# power.net
KiCad netlist of a schematic drawn in Altium Designer
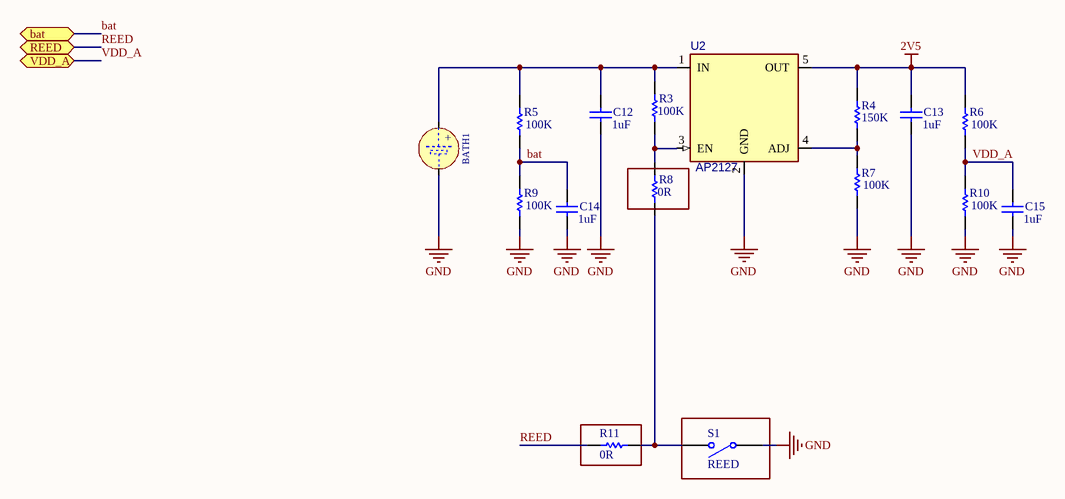
[diagram p0: power.SchDoc]

(export (version "E")
  (design (tool "Eeschema 10.0.6"))
  (components
    (comp (ref "BATH1")
      (value "~")
      (footprint "BATH_KEYSTONE_3000")
      (description "Battery Holder whit 2 Pin")
      (fields
        (field (name "PART NUMBER") "BATH_KEYSTONE_3000")
        (field (name "MANUFACTURER") "KEYSTONE")
        (field (name "AUTHOR") "CERN DEM JLC")
      )
      (libsource (lib "Eletro-mechanical") (part "Battery Holder 2 Pin"))
    )
    (comp (ref "C12")
      (value "1uF")
      (footprint "0805")
      (description "Ceramic Chip Capacitor - Standard")
      (fields (field (name "Comment") "C0805") (field (name "PUBLISHER") "Altium Limited"))
      (libsource (lib "KEMET Chip Capacitor") (part "C0805"))
    )
    (comp (ref "C13")
      (value "1uF")
      (footprint "0805")
      (description "Ceramic Chip Capacitor - Standard")
      (fields (field (name "Comment") "C0805") (field (name "PUBLISHER") "Altium Limited"))
      (libsource (lib "KEMET Chip Capacitor") (part "C0805"))
    )
    (comp (ref "C14")
      (value "1uF")
      (footprint "0805")
      (description "Ceramic Chip Capacitor - Standard")
      (fields (field (name "Comment") "C0805") (field (name "PUBLISHER") "Altium Limited"))
      (libsource (lib "KEMET Chip Capacitor") (part "C0805"))
    )
    (comp (ref "C15")
      (value "1uF")
      (footprint "0805")
      (description "Ceramic Chip Capacitor - Standard")
      (fields (field (name "Comment") "C0805") (field (name "PUBLISHER") "Altium Limited"))
      (libsource (lib "KEMET Chip Capacitor") (part "C0805"))
    )
    (comp (ref "R3")
      (value "100K")
      (footprint "ERA-0805")
      (fields (field (name "Comment") "ERA6Y") (field (name "PUBLISHER") "Altium Limited"))
      (libsource (lib "Panasonic Resistor_yeni") (part "ERA6Y"))
    )
    (comp (ref "R4")
      (value "150K")
      (footprint "ERA-0805")
      (fields (field (name "Comment") "ERA6Y") (field (name "PUBLISHER") "Altium Limited"))
      (libsource (lib "Panasonic Resistor_yeni") (part "ERA6Y"))
    )
    (comp (ref "R5")
      (value "100K")
      (footprint "ERA-0805")
      (fields (field (name "Comment") "ERA6Y") (field (name "PUBLISHER") "Altium Limited"))
      (libsource (lib "Panasonic Resistor_yeni") (part "ERA6Y"))
    )
    (comp (ref "R6")
      (value "100K")
      (footprint "ERA-0805")
      (fields (field (name "Comment") "ERA6Y") (field (name "PUBLISHER") "Altium Limited"))
      (libsource (lib "Panasonic Resistor_yeni") (part "ERA6Y"))
    )
    (comp (ref "R7")
      (value "100K")
      (footprint "ERA-0805")
      (fields (field (name "Comment") "ERA6Y") (field (name "PUBLISHER") "Altium Limited"))
      (libsource (lib "Panasonic Resistor_yeni") (part "ERA6Y"))
    )
    (comp (ref "R8")
      (value "0R")
      (footprint "ERA-0805")
      (fields (field (name "Comment") "ERA6Y") (field (name "PUBLISHER") "Altium Limited"))
      (libsource (lib "Panasonic Resistor_yeni") (part "ERA6Y"))
    )
    (comp (ref "R9")
      (value "100K")
      (footprint "ERA-0805")
      (fields (field (name "Comment") "ERA6Y") (field (name "PUBLISHER") "Altium Limited"))
      (libsource (lib "Panasonic Resistor_yeni") (part "ERA6Y"))
    )
    (comp (ref "R10")
      (value "100K")
      (footprint "ERA-0805")
      (fields (field (name "Comment") "ERA6Y") (field (name "PUBLISHER") "Altium Limited"))
      (libsource (lib "Panasonic Resistor_yeni") (part "ERA6Y"))
    )
    (comp (ref "R11")
      (value "0R")
      (footprint "ERA-0805")
      (fields (field (name "Comment") "ERA6Y") (field (name "PUBLISHER") "Altium Limited"))
      (libsource (lib "Panasonic Resistor_yeni") (part "ERA6Y"))
    )
    (comp (ref "S1")
      (value "REED")
      (footprint "SPST-2")
      (description "Single-Pole, Single-Throw Switch")
      (fields (field (name "PUBLISHER") "Altium Limited"))
      (libsource (lib "Miscellaneous Devices") (part "SW-SPST"))
    )
    (comp (ref "U2")
      (value "AP2127")
      (footprint "SOT-25")
      (description "LDO 300mA,  Low Quiescent Current, Fast Transient")
      (fields (field (name "Comment") "000000"))
      (libsource (lib "diodes-inc") (part "AP7331-WG"))
    )
  )
  (nets
    (net (code "1") (name "/REED") (class "Default")
      (node (ref "R11") (pin "2") (pinfunction "2_2") (pintype "passive"))
    )
    (net (code "2") (name "/VDD_A") (class "Default")
      (node (ref "C15") (pin "2") (pinfunction "2_2") (pintype "passive"))
      (node (ref "R10") (pin "2") (pinfunction "2_2") (pintype "passive"))
      (node (ref "R6") (pin "1") (pinfunction "1_1") (pintype "passive"))
    )
    (net (code "3") (name "/bat") (class "Default")
      (node (ref "C14") (pin "2") (pinfunction "2_2") (pintype "passive"))
      (node (ref "R5") (pin "1") (pinfunction "1_1") (pintype "passive"))
      (node (ref "R9") (pin "2") (pinfunction "2_2") (pintype "passive"))
    )
    (net (code "4") (name "2V5") (class "Default")
      (node (ref "C13") (pin "2") (pinfunction "2_2") (pintype "passive"))
      (node (ref "R4") (pin "2") (pinfunction "2_2") (pintype "passive"))
      (node (ref "R6") (pin "2") (pinfunction "2_2") (pintype "passive"))
      (node (ref "U2") (pin "5") (pinfunction "OUT_5") (pintype "power_in"))
    )
    (net (code "5") (name "GND") (class "Default")
      (node (ref "BATH1") (pin "2") (pinfunction "MINUS_2") (pintype "power_in"))
      (node (ref "C12") (pin "1") (pinfunction "1_1") (pintype "passive"))
      (node (ref "C13") (pin "1") (pinfunction "1_1") (pintype "passive"))
      (node (ref "C14") (pin "1") (pinfunction "1_1") (pintype "passive"))
      (node (ref "C15") (pin "1") (pinfunction "1_1") (pintype "passive"))
      (node (ref "R10") (pin "1") (pinfunction "1_1") (pintype "passive"))
      (node (ref "R7") (pin "1") (pinfunction "1_1") (pintype "passive"))
      (node (ref "R9") (pin "1") (pinfunction "1_1") (pintype "passive"))
      (node (ref "S1") (pin "1") (pinfunction "COMMON_1") (pintype "passive"))
      (node (ref "U2") (pin "2") (pinfunction "GND_2") (pintype "power_in"))
    )
    (net (code "6") (name "Net-(BATH1-PLUS)") (class "Default")
      (node (ref "BATH1") (pin "1") (pinfunction "PLUS_1") (pintype "power_in"))
      (node (ref "C12") (pin "2") (pinfunction "2_2") (pintype "passive"))
      (node (ref "R3") (pin "2") (pinfunction "2_2") (pintype "passive"))
      (node (ref "R5") (pin "2") (pinfunction "2_2") (pintype "passive"))
      (node (ref "U2") (pin "1") (pinfunction "IN_1") (pintype "power_in"))
    )
    (net (code "7") (name "Net-(S1-NO)") (class "Default")
      (node (ref "R11") (pin "1") (pinfunction "1_1") (pintype "passive"))
      (node (ref "R8") (pin "1") (pinfunction "1_1") (pintype "passive"))
      (node (ref "S1") (pin "2") (pinfunction "NO_2") (pintype "passive"))
    )
    (net (code "8") (name "Net-(U2-ADJ)") (class "Default")
      (node (ref "R4") (pin "1") (pinfunction "1_1") (pintype "passive"))
      (node (ref "R7") (pin "2") (pinfunction "2_2") (pintype "passive"))
      (node (ref "U2") (pin "4") (pinfunction "ADJ_4") (pintype "power_in"))
    )
    (net (code "9") (name "Net-(U2-EN)") (class "Default")
      (node (ref "R3") (pin "1") (pinfunction "1_1") (pintype "passive"))
      (node (ref "R8") (pin "2") (pinfunction "2_2") (pintype "passive"))
      (node (ref "U2") (pin "3") (pinfunction "EN_3") (pintype "input"))
    )
  )
)
